# Rov3_zasilanie_v3.net
KiCad netlist of a schematic drawn in EAGLE
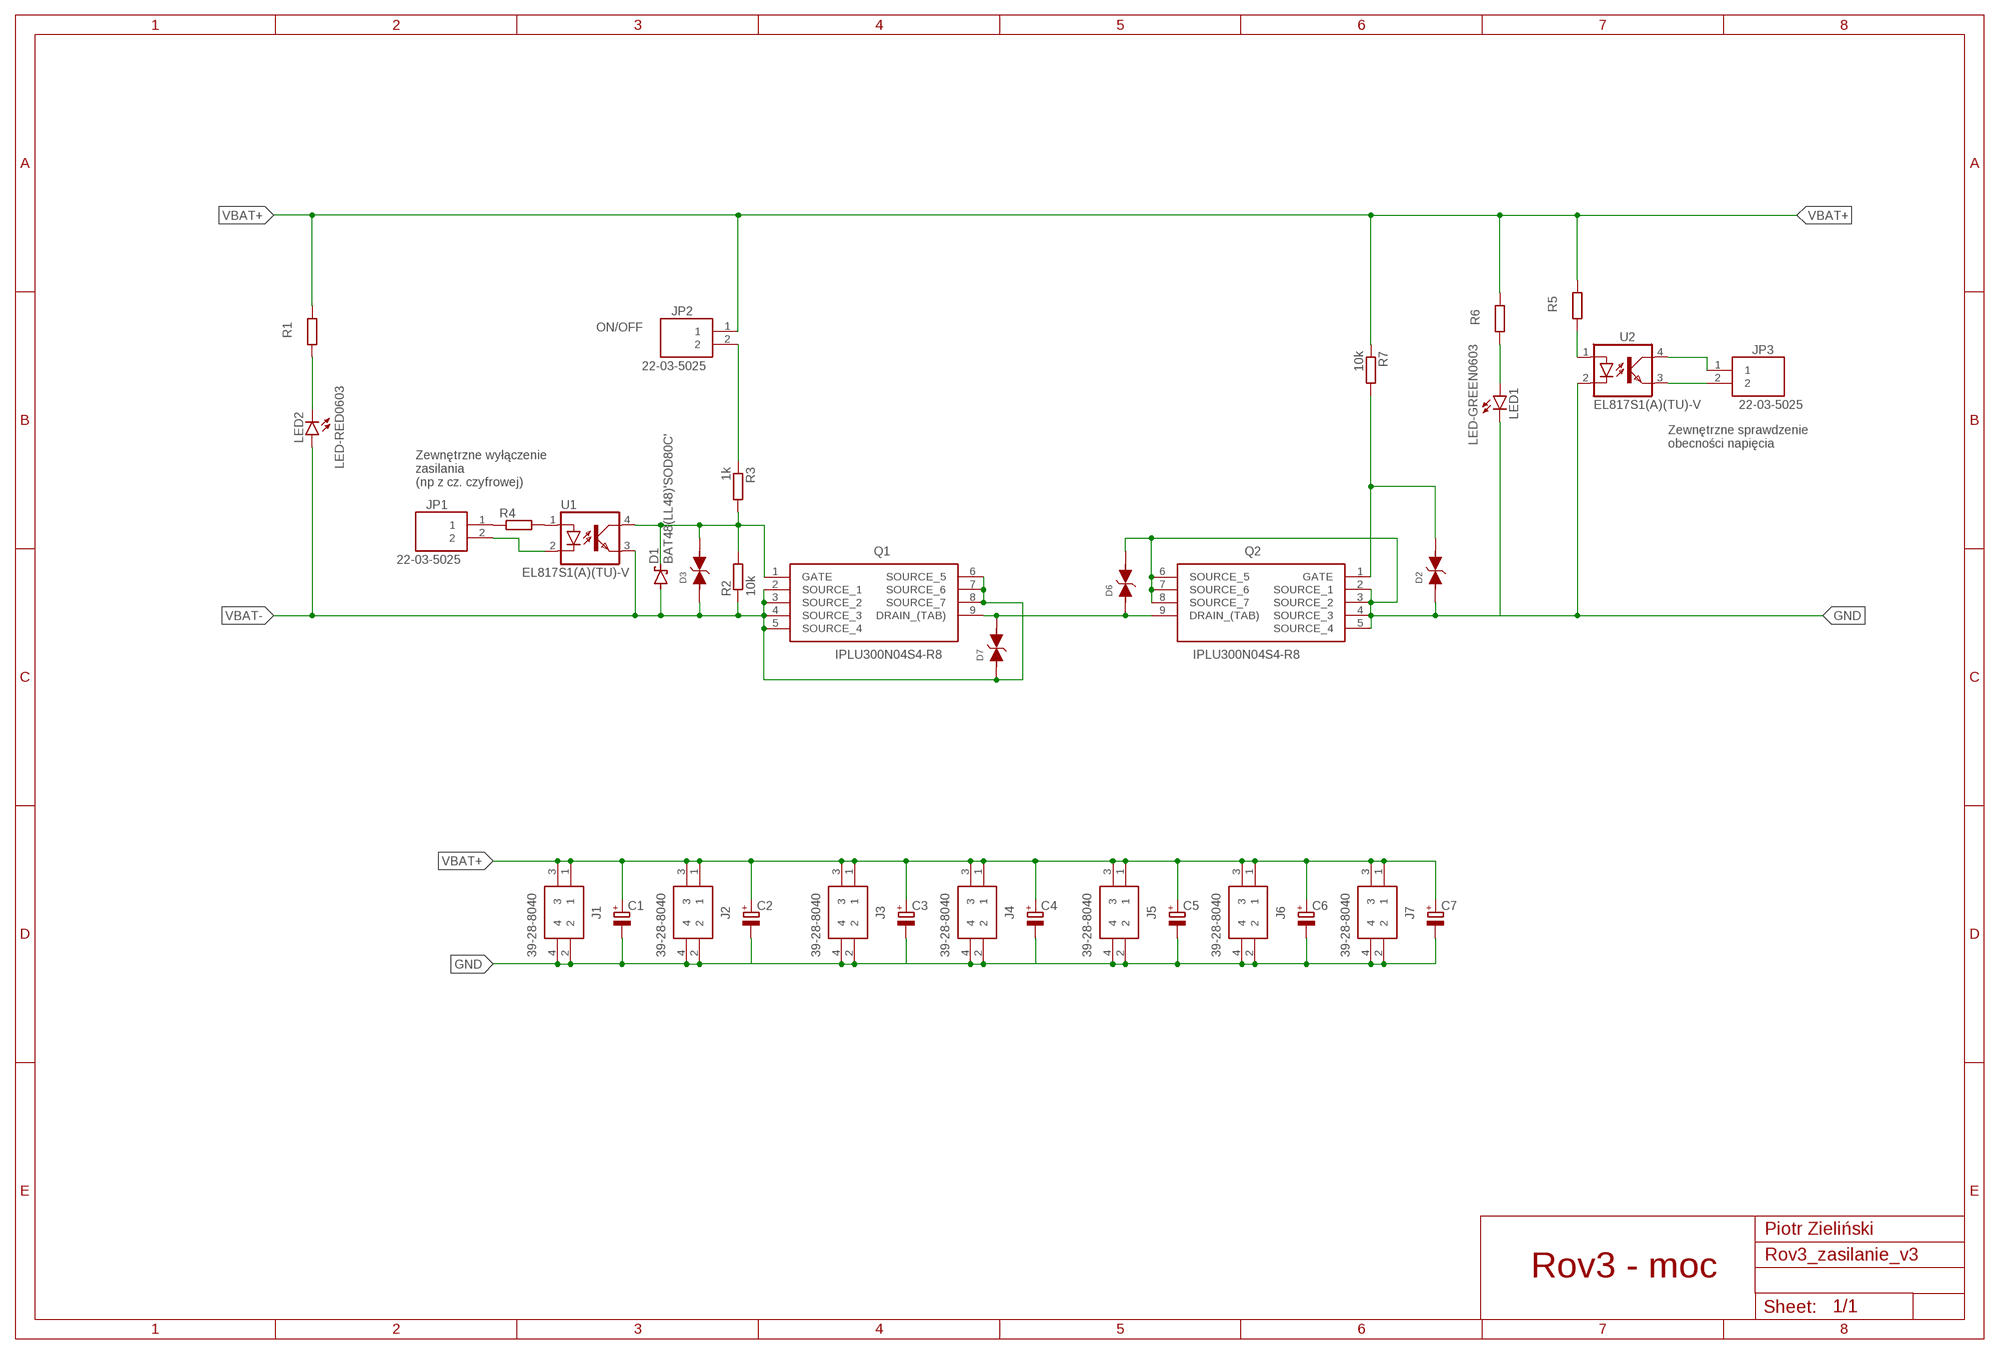
[diagram p0: schematic, sheet 1]

(export (version "E")
  (design (tool "Eeschema 10.0.6"))
  (components
    (comp (ref "C1")
      (value "CPOL-EUE5-10.5")
      (footprint "eagle-import:E5-10,5")
      (libsource (lib "eagle-import") (part "CPOL-EUE5-10.5"))
    )
    (comp (ref "C2")
      (value "CPOL-EUE5-10.5")
      (footprint "eagle-import:E5-10,5")
      (libsource (lib "eagle-import") (part "CPOL-EUE5-10.5"))
    )
    (comp (ref "C3")
      (value "CPOL-EUE5-10.5")
      (footprint "eagle-import:E5-10,5")
      (libsource (lib "eagle-import") (part "CPOL-EUE5-10.5"))
    )
    (comp (ref "C4")
      (value "CPOL-EUE5-10.5")
      (footprint "eagle-import:E5-10,5")
      (libsource (lib "eagle-import") (part "CPOL-EUE5-10.5"))
    )
    (comp (ref "C5")
      (value "CPOL-EUE5-10.5")
      (footprint "eagle-import:E5-10,5")
      (libsource (lib "eagle-import") (part "CPOL-EUE5-10.5"))
    )
    (comp (ref "C6")
      (value "CPOL-EUE5-10.5")
      (footprint "eagle-import:E5-10,5")
      (libsource (lib "eagle-import") (part "CPOL-EUE5-10.5"))
    )
    (comp (ref "C7")
      (value "CPOL-EUE5-10.5")
      (footprint "eagle-import:E5-10,5")
      (libsource (lib "eagle-import") (part "CPOL-EUE5-10.5"))
    )
    (comp (ref "D1")
      (value "BAT48(LL48)'SOD80C'")
      (footprint "eagle-import:SOD80C")
      (libsource (lib "eagle-import") (part "BAT48(LL48)'SOD80C'"))
    )
    (comp (ref "D2")
      (value "P6SMB20A_824501101")
      (footprint "eagle-import:VARTVSP_SMA_DO-214AC")
      (libsource (lib "eagle-import") (part "P6SMB20A_824501101"))
    )
    (comp (ref "D3")
      (value "P6SMB20A_824501101")
      (footprint "eagle-import:VARTVSP_SMA_DO-214AC")
      (libsource (lib "eagle-import") (part "P6SMB20A_824501101"))
    )
    (comp (ref "D6")
      (value "P6SMB20A_824501101")
      (footprint "eagle-import:VARTVSP_SMA_DO-214AC")
      (libsource (lib "eagle-import") (part "P6SMB20A_824501101"))
    )
    (comp (ref "D7")
      (value "P6SMB20A_824501101")
      (footprint "eagle-import:VARTVSP_SMA_DO-214AC")
      (libsource (lib "eagle-import") (part "P6SMB20A_824501101"))
    )
    (comp (ref "J1")
      (value "39-28-8040")
      (footprint "eagle-import:MOLEX_2X2_PCB_SOCKET")
      (fields (field (name "MOUSER_PART_NUMBER") "538-39-28-8040"))
      (libsource (lib "eagle-import") (part "39-28-8040"))
    )
    (comp (ref "J2")
      (value "39-28-8040")
      (footprint "eagle-import:MOLEX_2X2_PCB_SOCKET")
      (fields (field (name "MOUSER_PART_NUMBER") "538-39-28-8040"))
      (libsource (lib "eagle-import") (part "39-28-8040"))
    )
    (comp (ref "J3")
      (value "39-28-8040")
      (footprint "eagle-import:MOLEX_2X2_PCB_SOCKET")
      (fields (field (name "MOUSER_PART_NUMBER") "538-39-28-8040"))
      (libsource (lib "eagle-import") (part "39-28-8040"))
    )
    (comp (ref "J4")
      (value "39-28-8040")
      (footprint "eagle-import:MOLEX_2X2_PCB_SOCKET")
      (fields (field (name "MOUSER_PART_NUMBER") "538-39-28-8040"))
      (libsource (lib "eagle-import") (part "39-28-8040"))
    )
    (comp (ref "J5")
      (value "39-28-8040")
      (footprint "eagle-import:MOLEX_2X2_PCB_SOCKET")
      (fields (field (name "MOUSER_PART_NUMBER") "538-39-28-8040"))
      (libsource (lib "eagle-import") (part "39-28-8040"))
    )
    (comp (ref "J6")
      (value "39-28-8040")
      (footprint "eagle-import:MOLEX_2X2_PCB_SOCKET")
      (fields (field (name "MOUSER_PART_NUMBER") "538-39-28-8040"))
      (libsource (lib "eagle-import") (part "39-28-8040"))
    )
    (comp (ref "J7")
      (value "39-28-8040")
      (footprint "eagle-import:MOLEX_2X2_PCB_SOCKET")
      (fields (field (name "MOUSER_PART_NUMBER") "538-39-28-8040"))
      (libsource (lib "eagle-import") (part "39-28-8040"))
    )
    (comp (ref "JP1")
      (value "22-03-5025")
      (footprint "eagle-import:2.50MM_MINI-SPOX_2PIN_PCB_SOCKET")
      (fields (field (name "MOUSER_PART_NUMBER") "538-22-03-5025"))
      (libsource (lib "eagle-import") (part "22-03-5025"))
    )
    (comp (ref "JP2")
      (value "22-03-5025")
      (footprint "eagle-import:2.50MM_MINI-SPOX_2PIN_PCB_SOCKET")
      (fields (field (name "MOUSER_PART_NUMBER") "538-22-03-5025"))
      (libsource (lib "eagle-import") (part "22-03-5025"))
    )
    (comp (ref "JP3")
      (value "22-03-5025")
      (footprint "eagle-import:2.50MM_MINI-SPOX_2PIN_PCB_SOCKET")
      (fields (field (name "MOUSER_PART_NUMBER") "538-22-03-5025"))
      (libsource (lib "eagle-import") (part "22-03-5025"))
    )
    (comp (ref "LED1")
      (value "LED-GREEN0603")
      (footprint "eagle-import:0603-GREEN")
      (libsource (lib "eagle-import") (part "LED-GREEN0603"))
    )
    (comp (ref "LED2")
      (value "LED-RED0603")
      (footprint "eagle-import:0603-RED")
      (libsource (lib "eagle-import") (part "LED-RED0603"))
    )
    (comp (ref "Q1")
      (value "IPLU300N04S4-R8")
      (footprint "eagle-import:PG-HSOF-8-1")
      (fields (field (name "MOUSER_PART_NUMBER") "726-IPLU300N04S4-R8"))
      (libsource (lib "eagle-import") (part "IPLU300N04S4-R8"))
    )
    (comp (ref "Q2")
      (value "IPLU300N04S4-R8")
      (footprint "eagle-import:PG-HSOF-8-1")
      (fields (field (name "MOUSER_PART_NUMBER") "726-IPLU300N04S4-R8"))
      (libsource (lib "eagle-import") (part "IPLU300N04S4-R8"))
    )
    (comp (ref "R1")
      (value "R-EU_R0805")
      (footprint "eagle-import:R0805")
      (libsource (lib "eagle-import") (part "R-EU_R0805"))
    )
    (comp (ref "R2")
      (value "10k")
      (footprint "eagle-import:R0805")
      (libsource (lib "eagle-import") (part "R-EU_R0805"))
    )
    (comp (ref "R3")
      (value "1k")
      (footprint "eagle-import:R0805")
      (libsource (lib "eagle-import") (part "R-EU_R0805"))
    )
    (comp (ref "R4")
      (value "R-EU_R0805")
      (footprint "eagle-import:R0805")
      (libsource (lib "eagle-import") (part "R-EU_R0805"))
    )
    (comp (ref "R5")
      (value "R-EU_R0805")
      (footprint "eagle-import:R0805")
      (libsource (lib "eagle-import") (part "R-EU_R0805"))
    )
    (comp (ref "R6")
      (value "R-EU_R0805")
      (footprint "eagle-import:R0805")
      (libsource (lib "eagle-import") (part "R-EU_R0805"))
    )
    (comp (ref "R7")
      (value "10k")
      (footprint "eagle-import:R0805")
      (libsource (lib "eagle-import") (part "R-EU_R0805"))
    )
    (comp (ref "U1")
      (value "EL817S1(A)(TU)-V")
      (footprint "eagle-import:SOIC254P1030X390-4N_EL817S1(A)(TU)-V")
      (fields (field (name "MF") "Everlight Electronics") (field (name "MP") "EL817S1_A__TU_-V"))
      (libsource (lib "eagle-import") (part "EL817S1(A)(TU)-V"))
    )
    (comp (ref "U2")
      (value "EL817S1(A)(TU)-V")
      (footprint "eagle-import:SOIC254P1030X390-4N_EL817S1(A)(TU)-V")
      (fields (field (name "MF") "Everlight Electronics") (field (name "MP") "EL817S1_A__TU_-V"))
      (libsource (lib "eagle-import") (part "EL817S1(A)(TU)-V"))
    )
  )
  (nets
    (net (code "1") (name "GND") (class "Default")
      (node (ref "C1") (pin "-") (pinfunction "-_-") (pintype "passive"))
      (node (ref "C2") (pin "-") (pinfunction "-_-") (pintype "passive"))
      (node (ref "C3") (pin "-") (pinfunction "-_-") (pintype "passive"))
      (node (ref "C4") (pin "-") (pinfunction "-_-") (pintype "passive"))
      (node (ref "C5") (pin "-") (pinfunction "-_-") (pintype "passive"))
      (node (ref "C6") (pin "-") (pinfunction "-_-") (pintype "passive"))
      (node (ref "C7") (pin "-") (pinfunction "-_-") (pintype "passive"))
      (node (ref "D2") (pin "1") (pinfunction "1_1") (pintype "passive"))
      (node (ref "D6") (pin "2") (pinfunction "2_2") (pintype "passive"))
      (node (ref "J1") (pin "2") (pinfunction "2_2") (pintype "bidirectional"))
      (node (ref "J1") (pin "4") (pinfunction "4_4") (pintype "bidirectional"))
      (node (ref "J2") (pin "2") (pinfunction "2_2") (pintype "bidirectional"))
      (node (ref "J2") (pin "4") (pinfunction "4_4") (pintype "bidirectional"))
      (node (ref "J3") (pin "2") (pinfunction "2_2") (pintype "bidirectional"))
      (node (ref "J3") (pin "4") (pinfunction "4_4") (pintype "bidirectional"))
      (node (ref "J4") (pin "2") (pinfunction "2_2") (pintype "bidirectional"))
      (node (ref "J4") (pin "4") (pinfunction "4_4") (pintype "bidirectional"))
      (node (ref "J5") (pin "2") (pinfunction "2_2") (pintype "bidirectional"))
      (node (ref "J5") (pin "4") (pinfunction "4_4") (pintype "bidirectional"))
      (node (ref "J6") (pin "2") (pinfunction "2_2") (pintype "bidirectional"))
      (node (ref "J6") (pin "4") (pinfunction "4_4") (pintype "bidirectional"))
      (node (ref "J7") (pin "2") (pinfunction "2_2") (pintype "bidirectional"))
      (node (ref "J7") (pin "4") (pinfunction "4_4") (pintype "bidirectional"))
      (node (ref "LED1") (pin "C") (pinfunction "C_C") (pintype "passive"))
      (node (ref "Q2") (pin "2") (pinfunction "SOURCE_1_2") (pintype "bidirectional"))
      (node (ref "Q2") (pin "3") (pinfunction "SOURCE_2_3") (pintype "bidirectional"))
      (node (ref "Q2") (pin "4") (pinfunction "SOURCE_3_4") (pintype "bidirectional"))
      (node (ref "Q2") (pin "5") (pinfunction "SOURCE_4_5") (pintype "bidirectional"))
      (node (ref "Q2") (pin "6") (pinfunction "SOURCE_5_6") (pintype "bidirectional"))
      (node (ref "Q2") (pin "7") (pinfunction "SOURCE_6_7") (pintype "bidirectional"))
      (node (ref "Q2") (pin "8") (pinfunction "SOURCE_7_8") (pintype "bidirectional"))
      (node (ref "U2") (pin "2") (pinfunction "C_2") (pintype "passive"))
    )
    (net (code "2") (name "Net-(JP1-Pad1)") (class "Default")
      (node (ref "JP1") (pin "1") (pinfunction "1_1") (pintype "bidirectional"))
      (node (ref "R4") (pin "1") (pinfunction "1_1") (pintype "passive"))
    )
    (net (code "3") (name "Net-(JP2-Pad2)") (class "Default")
      (node (ref "JP2") (pin "2") (pinfunction "2_2") (pintype "bidirectional"))
      (node (ref "R3") (pin "1") (pinfunction "1_1") (pintype "passive"))
    )
    (net (code "4") (name "Net-(LED1-PadA)") (class "Default")
      (node (ref "LED1") (pin "A") (pinfunction "A_A") (pintype "passive"))
      (node (ref "R6") (pin "1") (pinfunction "1_1") (pintype "passive"))
    )
    (net (code "5") (name "Net-(LED2-PadC)") (class "Default")
      (node (ref "LED2") (pin "C") (pinfunction "C_C") (pintype "passive"))
      (node (ref "R1") (pin "1") (pinfunction "1_1") (pintype "passive"))
    )
    (net (code "6") (name "Net-(Q1-DRAIN_(TAB))") (class "Default")
      (node (ref "D6") (pin "1") (pinfunction "1_1") (pintype "passive"))
      (node (ref "D7") (pin "2") (pinfunction "2_2") (pintype "passive"))
      (node (ref "Q1") (pin "9") (pinfunction "DRAIN_(TAB)_9") (pintype "bidirectional"))
      (node (ref "Q2") (pin "9") (pinfunction "DRAIN_(TAB)_9") (pintype "bidirectional"))
    )
    (net (code "7") (name "Net-(Q1-GATE)") (class "Default")
      (node (ref "D1") (pin "C") (pinfunction "C_C") (pintype "passive"))
      (node (ref "D3") (pin "2") (pinfunction "2_2") (pintype "passive"))
      (node (ref "Q1") (pin "1") (pinfunction "GATE_1") (pintype "bidirectional"))
      (node (ref "R2") (pin "2") (pinfunction "2_2") (pintype "passive"))
      (node (ref "R3") (pin "2") (pinfunction "2_2") (pintype "passive"))
      (node (ref "U1") (pin "4") (pinfunction "COL_4") (pintype "passive"))
    )
    (net (code "8") (name "Net-(Q2-GATE)") (class "Default")
      (node (ref "D2") (pin "2") (pinfunction "2_2") (pintype "passive"))
      (node (ref "Q2") (pin "1") (pinfunction "GATE_1") (pintype "bidirectional"))
      (node (ref "R7") (pin "2") (pinfunction "2_2") (pintype "passive"))
    )
    (net (code "9") (name "Net-(U1-A)") (class "Default")
      (node (ref "R4") (pin "2") (pinfunction "2_2") (pintype "passive"))
      (node (ref "U1") (pin "1") (pinfunction "A_1") (pintype "passive"))
    )
    (net (code "10") (name "Net-(U1-C)") (class "Default")
      (node (ref "JP1") (pin "2") (pinfunction "2_2") (pintype "bidirectional"))
      (node (ref "U1") (pin "2") (pinfunction "C_2") (pintype "passive"))
    )
    (net (code "11") (name "Net-(U2-A)") (class "Default")
      (node (ref "R5") (pin "1") (pinfunction "1_1") (pintype "passive"))
      (node (ref "U2") (pin "1") (pinfunction "A_1") (pintype "passive"))
    )
    (net (code "12") (name "Net-(U2-COL)") (class "Default")
      (node (ref "JP3") (pin "1") (pinfunction "1_1") (pintype "bidirectional"))
      (node (ref "U2") (pin "4") (pinfunction "COL_4") (pintype "passive"))
    )
    (net (code "13") (name "Net-(U2-EMIT)") (class "Default")
      (node (ref "JP3") (pin "2") (pinfunction "2_2") (pintype "bidirectional"))
      (node (ref "U2") (pin "3") (pinfunction "EMIT_3") (pintype "passive"))
    )
    (net (code "14") (name "VBAT+") (class "Default")
      (node (ref "C1") (pin "+") (pinfunction "+_+") (pintype "passive"))
      (node (ref "C2") (pin "+") (pinfunction "+_+") (pintype "passive"))
      (node (ref "C3") (pin "+") (pinfunction "+_+") (pintype "passive"))
      (node (ref "C4") (pin "+") (pinfunction "+_+") (pintype "passive"))
      (node (ref "C5") (pin "+") (pinfunction "+_+") (pintype "passive"))
      (node (ref "C6") (pin "+") (pinfunction "+_+") (pintype "passive"))
      (node (ref "C7") (pin "+") (pinfunction "+_+") (pintype "passive"))
      (node (ref "J1") (pin "1") (pinfunction "1_1") (pintype "bidirectional"))
      (node (ref "J1") (pin "3") (pinfunction "3_3") (pintype "bidirectional"))
      (node (ref "J2") (pin "1") (pinfunction "1_1") (pintype "bidirectional"))
      (node (ref "J2") (pin "3") (pinfunction "3_3") (pintype "bidirectional"))
      (node (ref "J3") (pin "1") (pinfunction "1_1") (pintype "bidirectional"))
      (node (ref "J3") (pin "3") (pinfunction "3_3") (pintype "bidirectional"))
      (node (ref "J4") (pin "1") (pinfunction "1_1") (pintype "bidirectional"))
      (node (ref "J4") (pin "3") (pinfunction "3_3") (pintype "bidirectional"))
      (node (ref "J5") (pin "1") (pinfunction "1_1") (pintype "bidirectional"))
      (node (ref "J5") (pin "3") (pinfunction "3_3") (pintype "bidirectional"))
      (node (ref "J6") (pin "1") (pinfunction "1_1") (pintype "bidirectional"))
      (node (ref "J6") (pin "3") (pinfunction "3_3") (pintype "bidirectional"))
      (node (ref "J7") (pin "1") (pinfunction "1_1") (pintype "bidirectional"))
      (node (ref "J7") (pin "3") (pinfunction "3_3") (pintype "bidirectional"))
      (node (ref "JP2") (pin "1") (pinfunction "1_1") (pintype "bidirectional"))
      (node (ref "R1") (pin "2") (pinfunction "2_2") (pintype "passive"))
      (node (ref "R5") (pin "2") (pinfunction "2_2") (pintype "passive"))
      (node (ref "R6") (pin "2") (pinfunction "2_2") (pintype "passive"))
      (node (ref "R7") (pin "1") (pinfunction "1_1") (pintype "passive"))
    )
    (net (code "15") (name "VBAT-") (class "Default")
      (node (ref "D1") (pin "A") (pinfunction "A_A") (pintype "passive"))
      (node (ref "D3") (pin "1") (pinfunction "1_1") (pintype "passive"))
      (node (ref "D7") (pin "1") (pinfunction "1_1") (pintype "passive"))
      (node (ref "LED2") (pin "A") (pinfunction "A_A") (pintype "passive"))
      (node (ref "Q1") (pin "2") (pinfunction "SOURCE_1_2") (pintype "bidirectional"))
      (node (ref "Q1") (pin "3") (pinfunction "SOURCE_2_3") (pintype "bidirectional"))
      (node (ref "Q1") (pin "4") (pinfunction "SOURCE_3_4") (pintype "bidirectional"))
      (node (ref "Q1") (pin "5") (pinfunction "SOURCE_4_5") (pintype "bidirectional"))
      (node (ref "Q1") (pin "6") (pinfunction "SOURCE_5_6") (pintype "bidirectional"))
      (node (ref "Q1") (pin "7") (pinfunction "SOURCE_6_7") (pintype "bidirectional"))
      (node (ref "Q1") (pin "8") (pinfunction "SOURCE_7_8") (pintype "bidirectional"))
      (node (ref "R2") (pin "1") (pinfunction "1_1") (pintype "passive"))
      (node (ref "U1") (pin "3") (pinfunction "EMIT_3") (pintype "passive"))
    )
  )
)
